# Sch_Salah_Motor_Driver.net
KiCad netlist of a schematic drawn in Altium Designer
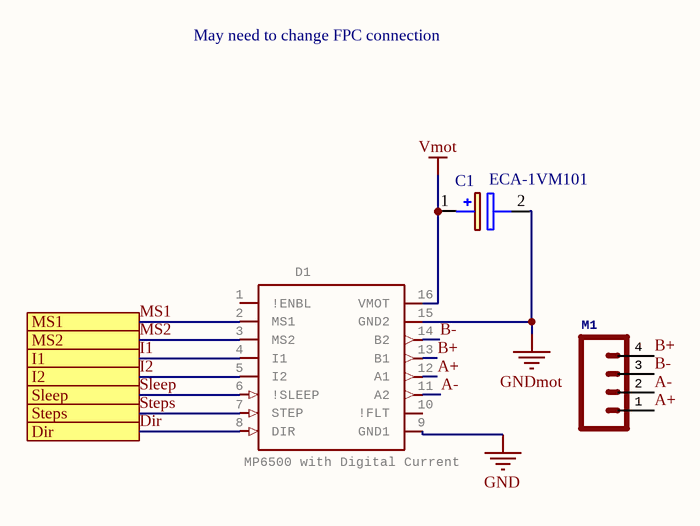
[diagram p0: Sch_Salah_Motor_Driver.SchDoc]

(export (version "E")
  (design (tool "Eeschema 10.0.6"))
  (components
    (comp (ref "C1")
      (value "ECA-1VM101")
      (footprint "SamacSys:CAPPRD250W55D655H1220")
      (description "Capacitor Polarised")
      (fields (field (name "MOUSER PART NUMBER") "667-ECA-1VM101"))
      (libsource (lib "*") (part "ECA-1VM101"))
    )
    (comp (ref "D1")
      (value "MP6500 with Digital Current")
      (footprint "MP6500")
      (fields (field (name "LIBRARYNAME") "pololu-stepper-driver"))
      (libsource (lib "pololu-stepper-driver.Library") (part "2969-MP6500"))
    )
    (comp (ref "M1")
      (value "~")
      (footprint "JST-4-PTH-VERT")
      (libsource (lib "SparkFun-Connectors") (part "CONN_04JST-PTH-VERT"))
    )
  )
  (nets
    (net (code "1") (name "/A+") (class "Default")
      (node (ref "D1") (pin "12") (pinfunction "A1_12") (pintype "output"))
      (node (ref "M1") (pin "1") (pinfunction "1_1") (pintype "passive"))
    )
    (net (code "2") (name "/A-") (class "Default")
      (node (ref "D1") (pin "11") (pinfunction "A2_11") (pintype "output"))
      (node (ref "M1") (pin "2") (pinfunction "2_2") (pintype "passive"))
    )
    (net (code "3") (name "/B+") (class "Default")
      (node (ref "D1") (pin "13") (pinfunction "B1_13") (pintype "output"))
      (node (ref "M1") (pin "4") (pinfunction "4_4") (pintype "passive"))
    )
    (net (code "4") (name "/B-") (class "Default")
      (node (ref "D1") (pin "14") (pinfunction "B2_14") (pintype "output"))
      (node (ref "M1") (pin "3") (pinfunction "3_3") (pintype "passive"))
    )
    (net (code "5") (name "/Dir") (class "Default")
      (node (ref "D1") (pin "8") (pinfunction "DIR_8") (pintype "input"))
    )
    (net (code "6") (name "/I1") (class "Default")
      (node (ref "D1") (pin "4") (pinfunction "I1_4") (pintype "passive"))
    )
    (net (code "7") (name "/I2") (class "Default")
      (node (ref "D1") (pin "5") (pinfunction "I2_5") (pintype "passive"))
    )
    (net (code "8") (name "/MS1") (class "Default")
      (node (ref "D1") (pin "2") (pinfunction "MS1_2") (pintype "passive"))
    )
    (net (code "9") (name "/MS2") (class "Default")
      (node (ref "D1") (pin "3") (pinfunction "MS2_3") (pintype "passive"))
    )
    (net (code "10") (name "/Sleep") (class "Default")
      (node (ref "D1") (pin "6") (pinfunction "!SLEEP_6") (pintype "input"))
    )
    (net (code "11") (name "/Steps") (class "Default")
      (node (ref "D1") (pin "7") (pinfunction "STEP_7") (pintype "input"))
    )
    (net (code "12") (name "GND") (class "Default")
      (node (ref "D1") (pin "9") (pinfunction "GND1_9") (pintype "power_in"))
    )
    (net (code "13") (name "GNDmot") (class "Default")
      (node (ref "C1") (pin "2") (pinfunction "-_2") (pintype "passive"))
      (node (ref "D1") (pin "15") (pinfunction "GND2_15") (pintype "power_in"))
    )
    (net (code "14") (name "Vmot") (class "Default")
      (node (ref "C1") (pin "1") (pinfunction "+_1") (pintype "passive"))
      (node (ref "D1") (pin "16") (pinfunction "VMOT_16") (pintype "power_in"))
    )
    (net (code "15") (name "unconnected-(D1-!ENBL-Pad1)") (class "Default")
      (node (ref "D1") (pin "1") (pinfunction "!ENBL_1") (pintype "passive"))
    )
    (net (code "16") (name "unconnected-(D1-!FLT-Pad10)") (class "Default")
      (node (ref "D1") (pin "10") (pinfunction "!FLT_10") (pintype "open_collector"))
    )
  )
)
